# board.net
KiCad netlist of a schematic drawn in EAGLE
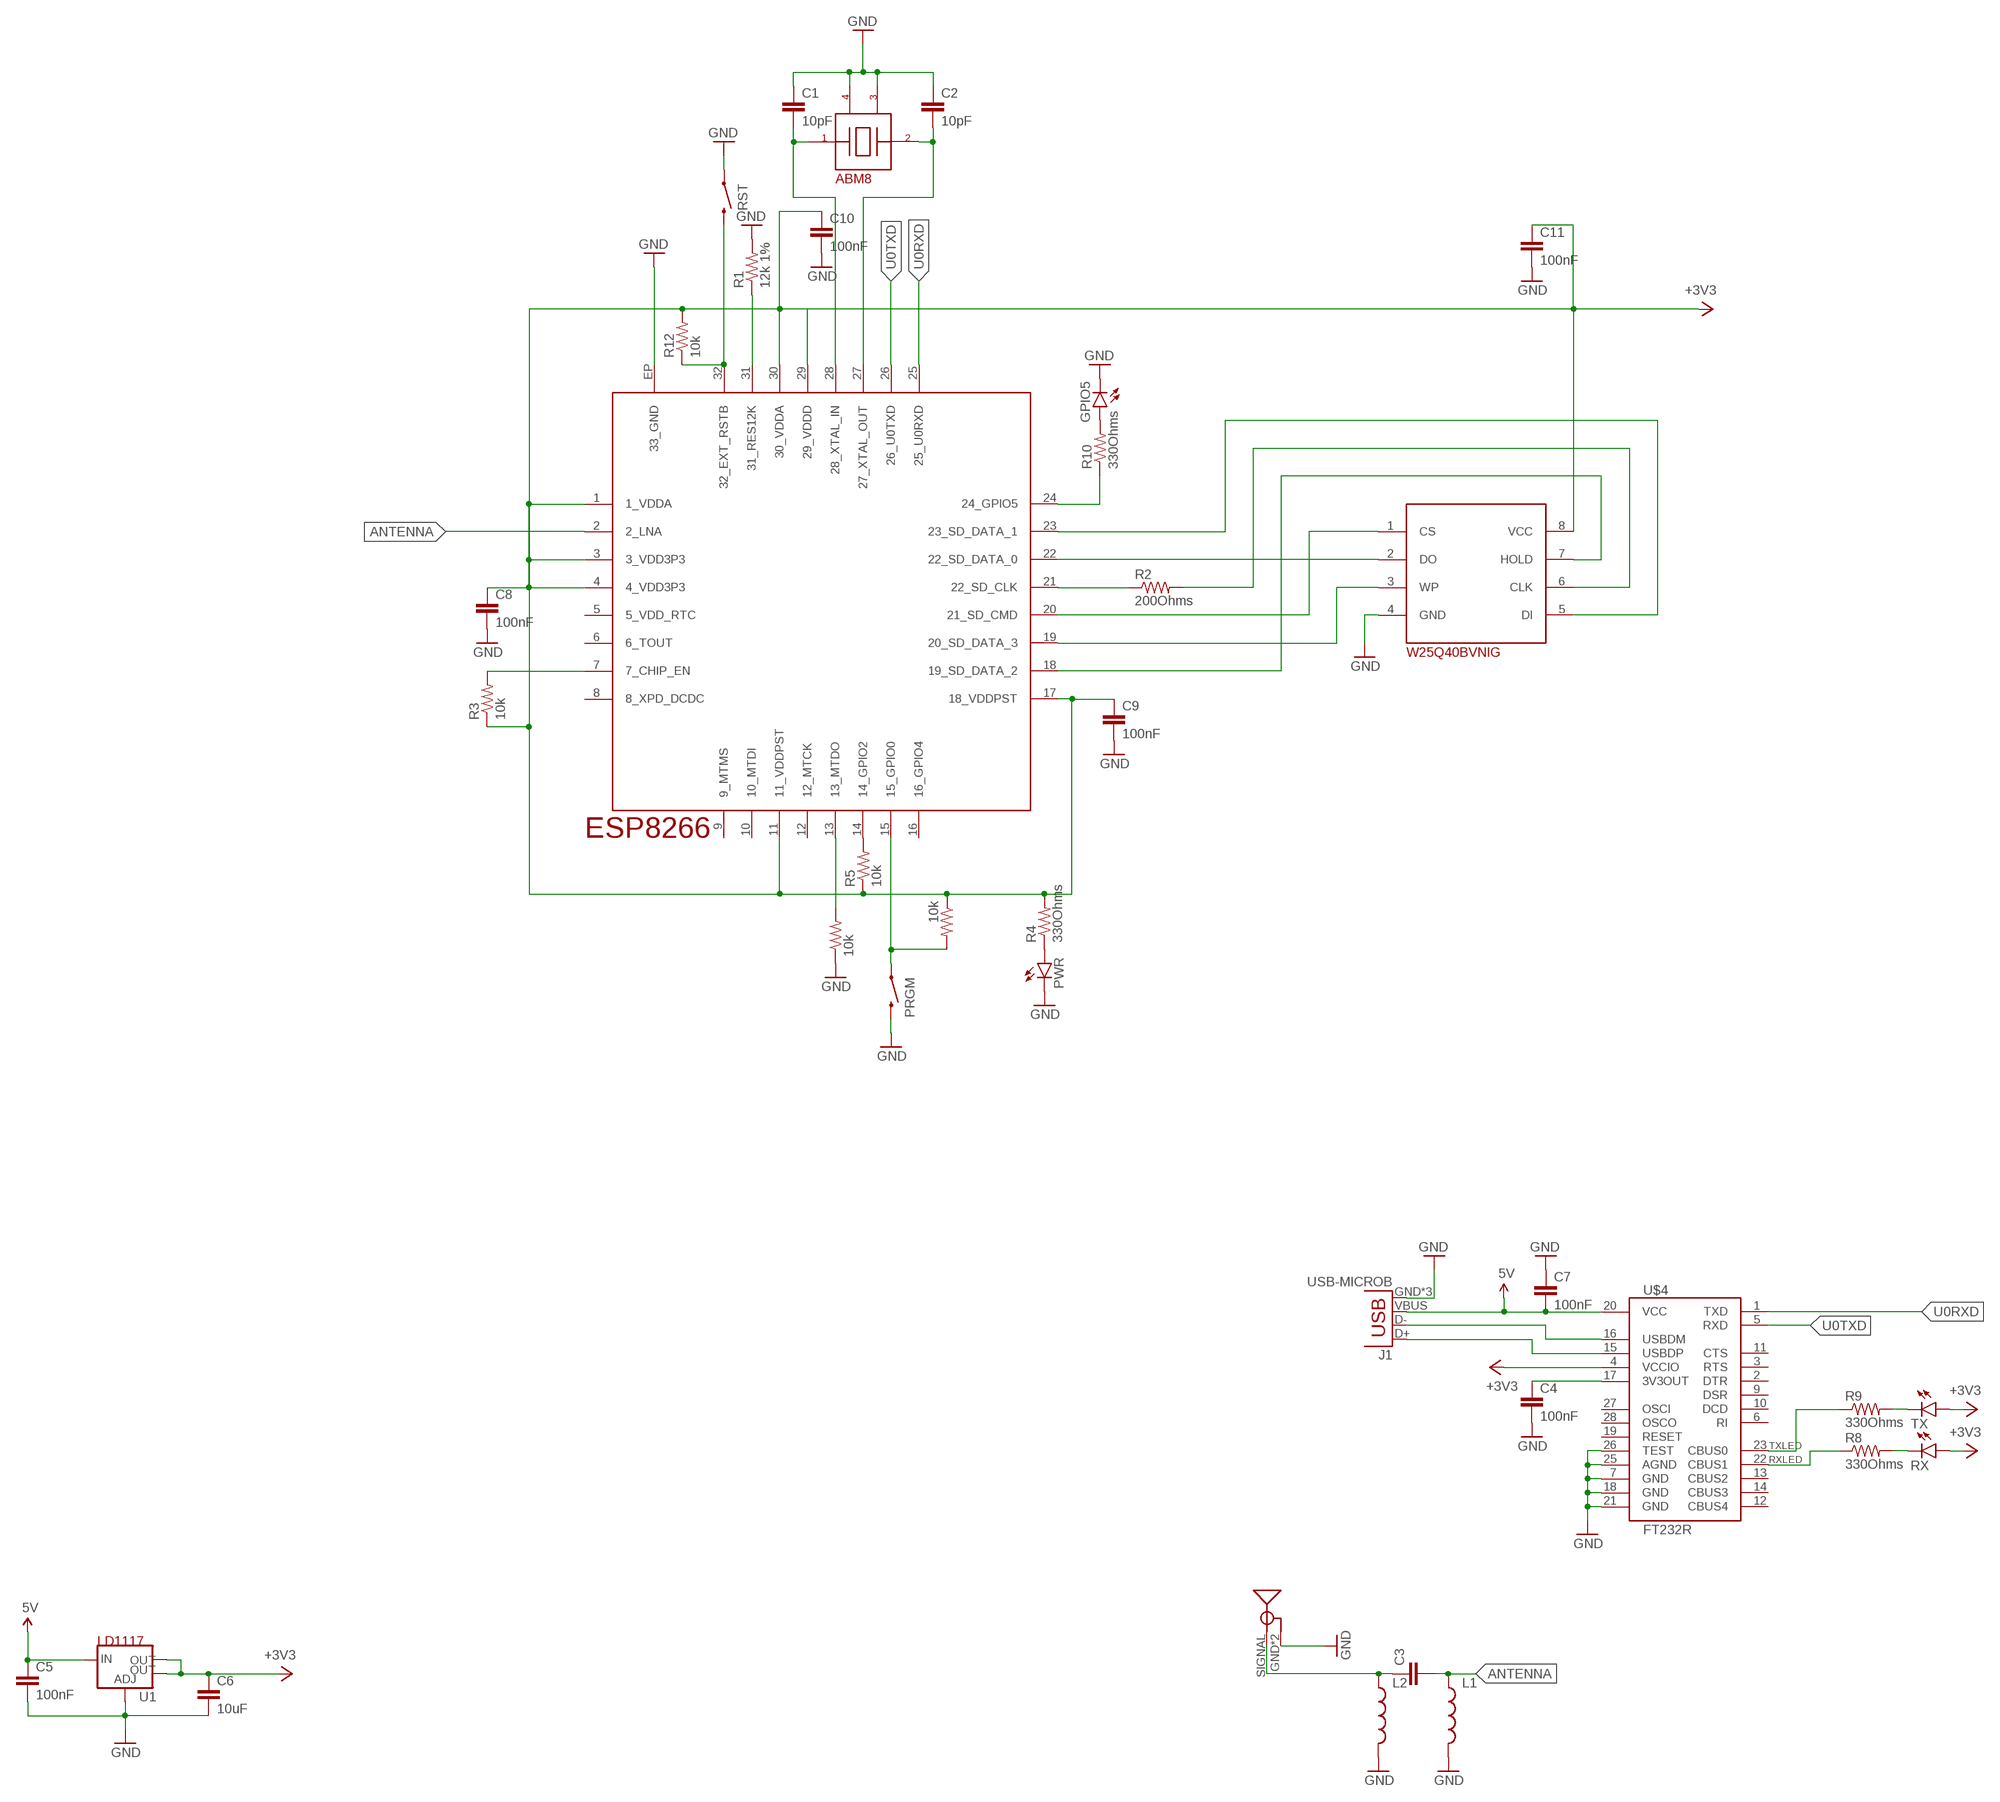
[diagram p0: schematic, sheet 1]

(export (version "E")
  (design (tool "Eeschema 10.0.6"))
  (components
    (comp (ref "C1")
      (value "10pF")
      (footprint "eagle-import:0603-CAP")
      (libsource (lib "eagle-import") (part "CAP0603-CAP"))
    )
    (comp (ref "C2")
      (value "10pF")
      (footprint "eagle-import:0603-CAP")
      (libsource (lib "eagle-import") (part "CAP0603-CAP"))
    )
    (comp (ref "C3")
      (value "CAP0402-CAP")
      (footprint "eagle-import:0402-CAP")
      (libsource (lib "eagle-import") (part "CAP0402-CAP"))
    )
    (comp (ref "C4")
      (value "100nF")
      (footprint "eagle-import:0603-CAP")
      (libsource (lib "eagle-import") (part "CAP0603-CAP"))
    )
    (comp (ref "C5")
      (value "100nF")
      (footprint "eagle-import:0603-CAP")
      (libsource (lib "eagle-import") (part "CAP0603-CAP"))
    )
    (comp (ref "C6")
      (value "10uF")
      (footprint "eagle-import:0603-CAP")
      (libsource (lib "eagle-import") (part "CAP0603-CAP"))
    )
    (comp (ref "C7")
      (value "100nF")
      (footprint "eagle-import:0603-CAP")
      (libsource (lib "eagle-import") (part "CAP0603-CAP"))
    )
    (comp (ref "C8")
      (value "100nF")
      (footprint "eagle-import:0603-CAP")
      (libsource (lib "eagle-import") (part "CAP0603-CAP"))
    )
    (comp (ref "C9")
      (value "100nF")
      (footprint "eagle-import:0603-CAP")
      (libsource (lib "eagle-import") (part "CAP0603-CAP"))
    )
    (comp (ref "C10")
      (value "100nF")
      (footprint "eagle-import:0603-CAP")
      (libsource (lib "eagle-import") (part "CAP0603-CAP"))
    )
    (comp (ref "C11")
      (value "100nF")
      (footprint "eagle-import:0603-CAP")
      (libsource (lib "eagle-import") (part "CAP0603-CAP"))
    )
    (comp (ref "GPIO5")
      (value "LED0603")
      (footprint "eagle-import:LED-0603")
      (libsource (lib "eagle-import") (part "LED0603"))
    )
    (comp (ref "J1")
      (value "USB-MICROB")
      (footprint "eagle-import:USB-MICROB")
      (libsource (lib "eagle-import") (part "USB-MICROB"))
    )
    (comp (ref "L1")
      (value "INDUCTOR0402")
      (footprint "eagle-import:C0402")
      (libsource (lib "eagle-import") (part "INDUCTOR0402"))
    )
    (comp (ref "L2")
      (value "INDUCTOR0402")
      (footprint "eagle-import:C0402")
      (libsource (lib "eagle-import") (part "INDUCTOR0402"))
    )
    (comp (ref "PRGM")
      (value "SWITCH-MOMENTARY-2PTH")
      (footprint "eagle-import:TACTILE-PTH")
      (libsource (lib "eagle-import") (part "SWITCH-MOMENTARY-2PTH"))
    )
    (comp (ref "PWR")
      (value "LED0603")
      (footprint "eagle-import:LED-0603")
      (libsource (lib "eagle-import") (part "LED0603"))
    )
    (comp (ref "R1")
      (value "12k 1%")
      (footprint "eagle-import:0603-RES")
      (libsource (lib "eagle-import") (part "12KOHM-1/10W-1%(0603)"))
    )
    (comp (ref "R2")
      (value "200Ohms")
      (footprint "eagle-import:0402-RES")
      (libsource (lib "eagle-import") (part "RESISTOR0402"))
    )
    (comp (ref "R3")
      (value "10k")
      (footprint "eagle-import:0603-RES")
      (libsource (lib "eagle-import") (part "RESISTOR0603-RES"))
    )
    (comp (ref "R4")
      (value "330Ohms")
      (footprint "eagle-import:0603-RES")
      (libsource (lib "eagle-import") (part "RESISTOR0603-RES"))
    )
    (comp (ref "R5")
      (value "10k")
      (footprint "eagle-import:0603-RES")
      (libsource (lib "eagle-import") (part "RESISTOR0603-RES"))
    )
    (comp (ref "R6")
      (value "10k")
      (footprint "eagle-import:0603-RES")
      (libsource (lib "eagle-import") (part "RESISTOR0603-RES"))
    )
    (comp (ref "R7")
      (value "10k")
      (footprint "eagle-import:0603-RES")
      (libsource (lib "eagle-import") (part "RESISTOR0603-RES"))
    )
    (comp (ref "R8")
      (value "330Ohms")
      (footprint "eagle-import:0603-RES")
      (libsource (lib "eagle-import") (part "RESISTOR0603-RES"))
    )
    (comp (ref "R9")
      (value "330Ohms")
      (footprint "eagle-import:0603-RES")
      (libsource (lib "eagle-import") (part "RESISTOR0603-RES"))
    )
    (comp (ref "R10")
      (value "330Ohms")
      (footprint "eagle-import:0603-RES")
      (libsource (lib "eagle-import") (part "RESISTOR0603-RES"))
    )
    (comp (ref "R12")
      (value "10k")
      (footprint "eagle-import:0603-RES")
      (libsource (lib "eagle-import") (part "RESISTOR0603-RES"))
    )
    (comp (ref "RST")
      (value "SWITCH-MOMENTARY-2PTH")
      (footprint "eagle-import:TACTILE-PTH")
      (libsource (lib "eagle-import") (part "SWITCH-MOMENTARY-2PTH"))
    )
    (comp (ref "RX")
      (value "LED0603")
      (footprint "eagle-import:LED-0603")
      (libsource (lib "eagle-import") (part "LED0603"))
    )
    (comp (ref "TX")
      (value "LED0603")
      (footprint "eagle-import:LED-0603")
      (libsource (lib "eagle-import") (part "LED0603"))
    )
    (comp (ref "U$1")
      (value "W25Q40BVNIG")
      (footprint "eagle-import:SOIC-8")
      (libsource (lib "eagle-import") (part "W25Q40BVNIG"))
    )
    (comp (ref "U$2")
      (value "ESP8266")
      (footprint "eagle-import:QFN-32")
      (libsource (lib "eagle-import") (part "ESP8266"))
    )
    (comp (ref "U$3")
      (value "ABM8")
      (footprint "eagle-import:ABM8")
      (libsource (lib "eagle-import") (part "ABM8"))
    )
    (comp (ref "U$4")
      (value "FT232R")
      (footprint "eagle-import:SSOP-28")
      (libsource (lib "eagle-import") (part "FT232R"))
    )
    (comp (ref "U$5")
      (value "OMNIANTENNA")
      (footprint "eagle-import:ANTENNA")
      (libsource (lib "eagle-import") (part "OMNIANTENNA"))
    )
    (comp (ref "U1")
      (value "V_REG_LM1117SOT223")
      (footprint "eagle-import:SOT223")
      (libsource (lib "eagle-import") (part "V_REG_LM1117SOT223"))
    )
  )
  (nets
    (net (code "1") (name "+3V3") (class "Default")
      (node (ref "C10") (pin "1") (pinfunction "1_1") (pintype "passive"))
      (node (ref "C11") (pin "1") (pinfunction "1_1") (pintype "passive"))
      (node (ref "C6") (pin "1") (pinfunction "1_1") (pintype "passive"))
      (node (ref "C8") (pin "1") (pinfunction "1_1") (pintype "passive"))
      (node (ref "C9") (pin "1") (pinfunction "1_1") (pintype "passive"))
      (node (ref "R12") (pin "2") (pinfunction "2_2") (pintype "passive"))
      (node (ref "R3") (pin "1") (pinfunction "1_1") (pintype "passive"))
      (node (ref "R4") (pin "2") (pinfunction "2_2") (pintype "passive"))
      (node (ref "R5") (pin "1") (pinfunction "1_1") (pintype "passive"))
      (node (ref "R6") (pin "1") (pinfunction "1_1") (pintype "passive"))
      (node (ref "RX") (pin "A") (pinfunction "A_A") (pintype "passive"))
      (node (ref "TX") (pin "A") (pinfunction "A_A") (pintype "passive"))
      (node (ref "U$1") (pin "8") (pinfunction "VCC_8") (pintype "bidirectional"))
      (node (ref "U$2") (pin "1") (pinfunction "1_VDDA_1") (pintype "bidirectional"))
      (node (ref "U$2") (pin "11") (pinfunction "11_VDDPST_11") (pintype "bidirectional"))
      (node (ref "U$2") (pin "17") (pinfunction "18_VDDPST_17") (pintype "bidirectional"))
      (node (ref "U$2") (pin "29") (pinfunction "29_VDDD_29") (pintype "bidirectional"))
      (node (ref "U$2") (pin "3") (pinfunction "3_VDD3P3_3") (pintype "bidirectional"))
      (node (ref "U$2") (pin "30") (pinfunction "30_VDDA_30") (pintype "bidirectional"))
      (node (ref "U$2") (pin "4") (pinfunction "4_VDD3P3_4") (pintype "bidirectional"))
      (node (ref "U$4") (pin "4") (pinfunction "VCCIO_4") (pintype "power_in"))
      (node (ref "U1") (pin "2") (pinfunction "OUT_2") (pintype "output"))
      (node (ref "U1") (pin "4") (pinfunction "OUT_4") (pintype "output"))
    )
    (net (code "2") (name "5V") (class "Default")
      (node (ref "C5") (pin "1") (pinfunction "1_1") (pintype "passive"))
      (node (ref "C7") (pin "2") (pinfunction "2_2") (pintype "passive"))
      (node (ref "J1") (pin "VBUS") (pinfunction "VBUS_VBUS") (pintype "bidirectional"))
      (node (ref "U$4") (pin "20") (pinfunction "VCC_20") (pintype "power_in"))
      (node (ref "U1") (pin "3") (pinfunction "IN_3") (pintype "input"))
    )
    (net (code "3") (name "ANTENNA") (class "Default")
      (node (ref "C3") (pin "2") (pinfunction "2_2") (pintype "passive"))
      (node (ref "L1") (pin "1") (pinfunction "1_1") (pintype "passive"))
      (node (ref "U$2") (pin "2") (pinfunction "2_LNA_2") (pintype "bidirectional"))
    )
    (net (code "4") (name "GND") (class "Default")
      (node (ref "C1") (pin "1") (pinfunction "1_1") (pintype "passive"))
      (node (ref "C10") (pin "2") (pinfunction "2_2") (pintype "passive"))
      (node (ref "C11") (pin "2") (pinfunction "2_2") (pintype "passive"))
      (node (ref "C2") (pin "1") (pinfunction "1_1") (pintype "passive"))
      (node (ref "C4") (pin "2") (pinfunction "2_2") (pintype "passive"))
      (node (ref "C5") (pin "2") (pinfunction "2_2") (pintype "passive"))
      (node (ref "C6") (pin "2") (pinfunction "2_2") (pintype "passive"))
      (node (ref "C7") (pin "1") (pinfunction "1_1") (pintype "passive"))
      (node (ref "C8") (pin "2") (pinfunction "2_2") (pintype "passive"))
      (node (ref "C9") (pin "2") (pinfunction "2_2") (pintype "passive"))
      (node (ref "GPIO5") (pin "C") (pinfunction "C_C") (pintype "passive"))
      (node (ref "J1") (pin "GND") (pinfunction "GND_GND") (pintype "bidirectional"))
      (node (ref "J1") (pin "MT1") (pinfunction "GND_MT1") (pintype "bidirectional"))
      (node (ref "J1") (pin "MT2") (pinfunction "GND_MT2") (pintype "bidirectional"))
      (node (ref "L1") (pin "2") (pinfunction "2_2") (pintype "passive"))
      (node (ref "L2") (pin "2") (pinfunction "2_2") (pintype "passive"))
      (node (ref "PRGM") (pin "3") (pinfunction "2_3") (pintype "passive"))
      (node (ref "PWR") (pin "C") (pinfunction "C_C") (pintype "passive"))
      (node (ref "R1") (pin "2") (pinfunction "2_2") (pintype "passive"))
      (node (ref "R7") (pin "1") (pinfunction "1_1") (pintype "passive"))
      (node (ref "RST") (pin "1") (pinfunction "1_1") (pintype "passive"))
      (node (ref "U$1") (pin "4") (pinfunction "GND_4") (pintype "bidirectional"))
      (node (ref "U$2") (pin "EP") (pinfunction "33_GND_EP") (pintype "bidirectional"))
      (node (ref "U$3") (pin "P$2") (pinfunction "GND_P$2") (pintype "bidirectional"))
      (node (ref "U$3") (pin "P$4") (pinfunction "GND2_P$4") (pintype "bidirectional"))
      (node (ref "U$4") (pin "18") (pinfunction "GND_18") (pintype "power_in"))
      (node (ref "U$4") (pin "21") (pinfunction "GND_21") (pintype "power_in"))
      (node (ref "U$4") (pin "25") (pinfunction "AGND_25") (pintype "power_in"))
      (node (ref "U$4") (pin "26") (pinfunction "TEST_26") (pintype "input"))
      (node (ref "U$4") (pin "7") (pinfunction "GND_7") (pintype "power_in"))
      (node (ref "U$5") (pin "GND") (pinfunction "GND_GND") (pintype "bidirectional"))
      (node (ref "U$5") (pin "GND1") (pinfunction "GND_GND1") (pintype "bidirectional"))
      (node (ref "U1") (pin "1") (pinfunction "ADJ_1") (pintype "input"))
    )
    (net (code "5") (name "Net-(C3-Pad1)") (class "Default")
      (node (ref "C3") (pin "1") (pinfunction "1_1") (pintype "passive"))
      (node (ref "L2") (pin "1") (pinfunction "1_1") (pintype "passive"))
      (node (ref "U$5") (pin "SIGNAL") (pinfunction "SIGNAL_SIGNAL") (pintype "bidirectional"))
    )
    (net (code "6") (name "Net-(GPIO5-PadA)") (class "Default")
      (node (ref "GPIO5") (pin "A") (pinfunction "A_A") (pintype "passive"))
      (node (ref "R10") (pin "2") (pinfunction "2_2") (pintype "passive"))
    )
    (net (code "7") (name "Net-(PWR-PadA)") (class "Default")
      (node (ref "PWR") (pin "A") (pinfunction "A_A") (pintype "passive"))
      (node (ref "R4") (pin "1") (pinfunction "1_1") (pintype "passive"))
    )
    (net (code "8") (name "Net-(R8-Pad2)") (class "Default")
      (node (ref "R8") (pin "2") (pinfunction "2_2") (pintype "passive"))
      (node (ref "RX") (pin "C") (pinfunction "C_C") (pintype "passive"))
    )
    (net (code "9") (name "Net-(R9-Pad2)") (class "Default")
      (node (ref "R9") (pin "2") (pinfunction "2_2") (pintype "passive"))
      (node (ref "TX") (pin "C") (pinfunction "C_C") (pintype "passive"))
    )
    (net (code "10") (name "Net-(RST-2)") (class "Default")
      (node (ref "R12") (pin "1") (pinfunction "1_1") (pintype "passive"))
      (node (ref "RST") (pin "3") (pinfunction "2_3") (pintype "passive"))
      (node (ref "U$2") (pin "32") (pinfunction "32_EXT_RSTB_32") (pintype "bidirectional"))
    )
    (net (code "11") (name "Net-(U$1-CLK)") (class "Default")
      (node (ref "R2") (pin "2") (pinfunction "2_2") (pintype "passive"))
      (node (ref "U$1") (pin "6") (pinfunction "CLK_6") (pintype "bidirectional"))
    )
    (net (code "12") (name "Net-(U$1-CS)") (class "Default")
      (node (ref "U$1") (pin "1") (pinfunction "CS_1") (pintype "bidirectional"))
      (node (ref "U$2") (pin "20") (pinfunction "21_SD_CMD_20") (pintype "bidirectional"))
    )
    (net (code "13") (name "Net-(U$1-DI)") (class "Default")
      (node (ref "U$1") (pin "5") (pinfunction "DI_5") (pintype "bidirectional"))
      (node (ref "U$2") (pin "23") (pinfunction "23_SD_DATA_1_23") (pintype "bidirectional"))
    )
    (net (code "14") (name "Net-(U$1-DO)") (class "Default")
      (node (ref "U$1") (pin "2") (pinfunction "DO_2") (pintype "bidirectional"))
      (node (ref "U$2") (pin "22") (pinfunction "22_SD_DATA_0_22") (pintype "bidirectional"))
    )
    (net (code "15") (name "Net-(U$1-HOLD)") (class "Default")
      (node (ref "U$1") (pin "7") (pinfunction "HOLD_7") (pintype "bidirectional"))
      (node (ref "U$2") (pin "18") (pinfunction "19_SD_DATA_2_18") (pintype "bidirectional"))
    )
    (net (code "16") (name "Net-(U$1-WP)") (class "Default")
      (node (ref "U$1") (pin "3") (pinfunction "WP_3") (pintype "bidirectional"))
      (node (ref "U$2") (pin "19") (pinfunction "20_SD_DATA_3_19") (pintype "bidirectional"))
    )
    (net (code "17") (name "Net-(U$2-7_CHIP_EN)") (class "Default")
      (node (ref "R3") (pin "2") (pinfunction "2_2") (pintype "passive"))
      (node (ref "U$2") (pin "7") (pinfunction "7_CHIP_EN_7") (pintype "bidirectional"))
    )
    (net (code "18") (name "Net-(U$2-13_MTDO)") (class "Default")
      (node (ref "R7") (pin "2") (pinfunction "2_2") (pintype "passive"))
      (node (ref "U$2") (pin "13") (pinfunction "13_MTDO_13") (pintype "bidirectional"))
    )
    (net (code "19") (name "Net-(U$2-14_GPIO2)") (class "Default")
      (node (ref "R5") (pin "2") (pinfunction "2_2") (pintype "passive"))
      (node (ref "U$2") (pin "14") (pinfunction "14_GPIO2_14") (pintype "bidirectional"))
    )
    (net (code "20") (name "Net-(U$2-15_GPIO0)") (class "Default")
      (node (ref "PRGM") (pin "1") (pinfunction "1_1") (pintype "passive"))
      (node (ref "R6") (pin "2") (pinfunction "2_2") (pintype "passive"))
      (node (ref "U$2") (pin "15") (pinfunction "15_GPIO0_15") (pintype "bidirectional"))
    )
    (net (code "21") (name "Net-(U$2-22_SD_CLK)") (class "Default")
      (node (ref "R2") (pin "1") (pinfunction "1_1") (pintype "passive"))
      (node (ref "U$2") (pin "21") (pinfunction "22_SD_CLK_21") (pintype "bidirectional"))
    )
    (net (code "22") (name "Net-(U$2-24_GPIO5)") (class "Default")
      (node (ref "R10") (pin "1") (pinfunction "1_1") (pintype "passive"))
      (node (ref "U$2") (pin "24") (pinfunction "24_GPIO5_24") (pintype "bidirectional"))
    )
    (net (code "23") (name "Net-(U$2-27_XTAL_OUT)") (class "Default")
      (node (ref "C2") (pin "2") (pinfunction "2_2") (pintype "passive"))
      (node (ref "U$2") (pin "27") (pinfunction "27_XTAL_OUT_27") (pintype "bidirectional"))
      (node (ref "U$3") (pin "P$3") (pinfunction "OUT_P$3") (pintype "bidirectional"))
    )
    (net (code "24") (name "Net-(U$2-28_XTAL_IN)") (class "Default")
      (node (ref "C1") (pin "2") (pinfunction "2_2") (pintype "passive"))
      (node (ref "U$2") (pin "28") (pinfunction "28_XTAL_IN_28") (pintype "bidirectional"))
      (node (ref "U$3") (pin "P$1") (pinfunction "IN_P$1") (pintype "bidirectional"))
    )
    (net (code "25") (name "Net-(U$2-31_RES12K)") (class "Default")
      (node (ref "R1") (pin "1") (pinfunction "1_1") (pintype "passive"))
      (node (ref "U$2") (pin "31") (pinfunction "31_RES12K_31") (pintype "bidirectional"))
    )
    (net (code "26") (name "Net-(U$4-3V3OUT)") (class "Default")
      (node (ref "C4") (pin "1") (pinfunction "1_1") (pintype "passive"))
      (node (ref "U$4") (pin "17") (pinfunction "3V3OUT_17") (pintype "output"))
    )
    (net (code "27") (name "Net-(U$4-CBUS0)") (class "Default")
      (node (ref "R9") (pin "1") (pinfunction "1_1") (pintype "passive"))
      (node (ref "U$4") (pin "23") (pinfunction "CBUS0_23") (pintype "input"))
    )
    (net (code "28") (name "Net-(U$4-CBUS1)") (class "Default")
      (node (ref "R8") (pin "1") (pinfunction "1_1") (pintype "passive"))
      (node (ref "U$4") (pin "22") (pinfunction "CBUS1_22") (pintype "input"))
    )
    (net (code "29") (name "Net-(U$4-USBDM)") (class "Default")
      (node (ref "J1") (pin "D-") (pinfunction "D-_D-") (pintype "bidirectional"))
      (node (ref "U$4") (pin "16") (pinfunction "USBDM_16") (pintype "bidirectional"))
    )
    (net (code "30") (name "Net-(U$4-USBDP)") (class "Default")
      (node (ref "J1") (pin "D+") (pinfunction "D+_D+") (pintype "bidirectional"))
      (node (ref "U$4") (pin "15") (pinfunction "USBDP_15") (pintype "bidirectional"))
    )
    (net (code "31") (name "U0RXD") (class "Default")
      (node (ref "U$2") (pin "25") (pinfunction "25_U0RXD_25") (pintype "bidirectional"))
      (node (ref "U$4") (pin "1") (pinfunction "TXD_1") (pintype "output"))
    )
    (net (code "32") (name "U0TXD") (class "Default")
      (node (ref "U$2") (pin "26") (pinfunction "26_U0TXD_26") (pintype "bidirectional"))
      (node (ref "U$4") (pin "5") (pinfunction "RXD_5") (pintype "input"))
    )
    (net (code "33") (name "unconnected-(U$2-5_VDD_RTC-Pad5)") (class "Default")
      (node (ref "U$2") (pin "5") (pinfunction "5_VDD_RTC_5") (pintype "bidirectional"))
    )
    (net (code "34") (name "unconnected-(U$2-6_TOUT-Pad6)") (class "Default")
      (node (ref "U$2") (pin "6") (pinfunction "6_TOUT_6") (pintype "bidirectional"))
    )
    (net (code "35") (name "unconnected-(U$2-8_XPD_DCDC-Pad8)") (class "Default")
      (node (ref "U$2") (pin "8") (pinfunction "8_XPD_DCDC_8") (pintype "bidirectional"))
    )
    (net (code "36") (name "unconnected-(U$2-9_MTMS-Pad9)") (class "Default")
      (node (ref "U$2") (pin "9") (pinfunction "9_MTMS_9") (pintype "bidirectional"))
    )
    (net (code "37") (name "unconnected-(U$2-10_MTDI-Pad10)") (class "Default")
      (node (ref "U$2") (pin "10") (pinfunction "10_MTDI_10") (pintype "bidirectional"))
    )
    (net (code "38") (name "unconnected-(U$2-12_MTCK-Pad12)") (class "Default")
      (node (ref "U$2") (pin "12") (pinfunction "12_MTCK_12") (pintype "bidirectional"))
    )
    (net (code "39") (name "unconnected-(U$2-16_GPIO4-Pad16)") (class "Default")
      (node (ref "U$2") (pin "16") (pinfunction "16_GPIO4_16") (pintype "bidirectional"))
    )
    (net (code "40") (name "unconnected-(U$4-CBUS2-Pad13)") (class "Default")
      (node (ref "U$4") (pin "13") (pinfunction "CBUS2_13") (pintype "input"))
    )
    (net (code "41") (name "unconnected-(U$4-CBUS3-Pad14)") (class "Default")
      (node (ref "U$4") (pin "14") (pinfunction "CBUS3_14") (pintype "input"))
    )
    (net (code "42") (name "unconnected-(U$4-CBUS4-Pad12)") (class "Default")
      (node (ref "U$4") (pin "12") (pinfunction "CBUS4_12") (pintype "input"))
    )
    (net (code "43") (name "unconnected-(U$4-CTS-Pad11)") (class "Default")
      (node (ref "U$4") (pin "11") (pinfunction "CTS_11") (pintype "input"))
    )
    (net (code "44") (name "unconnected-(U$4-DCD-Pad10)") (class "Default")
      (node (ref "U$4") (pin "10") (pinfunction "DCD_10") (pintype "input"))
    )
    (net (code "45") (name "unconnected-(U$4-DSR-Pad9)") (class "Default")
      (node (ref "U$4") (pin "9") (pinfunction "DSR_9") (pintype "input"))
    )
    (net (code "46") (name "unconnected-(U$4-DTR-Pad2)") (class "Default")
      (node (ref "U$4") (pin "2") (pinfunction "DTR_2") (pintype "output"))
    )
    (net (code "47") (name "unconnected-(U$4-OSCI-Pad27)") (class "Default")
      (node (ref "U$4") (pin "27") (pinfunction "OSCI_27") (pintype "input"))
    )
    (net (code "48") (name "unconnected-(U$4-OSCO-Pad28)") (class "Default")
      (node (ref "U$4") (pin "28") (pinfunction "OSCO_28") (pintype "output"))
    )
    (net (code "49") (name "unconnected-(U$4-RESET-Pad19)") (class "Default")
      (node (ref "U$4") (pin "19") (pinfunction "RESET_19") (pintype "input"))
    )
    (net (code "50") (name "unconnected-(U$4-RI-Pad6)") (class "Default")
      (node (ref "U$4") (pin "6") (pinfunction "RI_6") (pintype "input"))
    )
    (net (code "51") (name "unconnected-(U$4-RTS-Pad3)") (class "Default")
      (node (ref "U$4") (pin "3") (pinfunction "RTS_3") (pintype "output"))
    )
  )
)
